# piboy.net
KiCad netlist of a schematic drawn in EAGLE
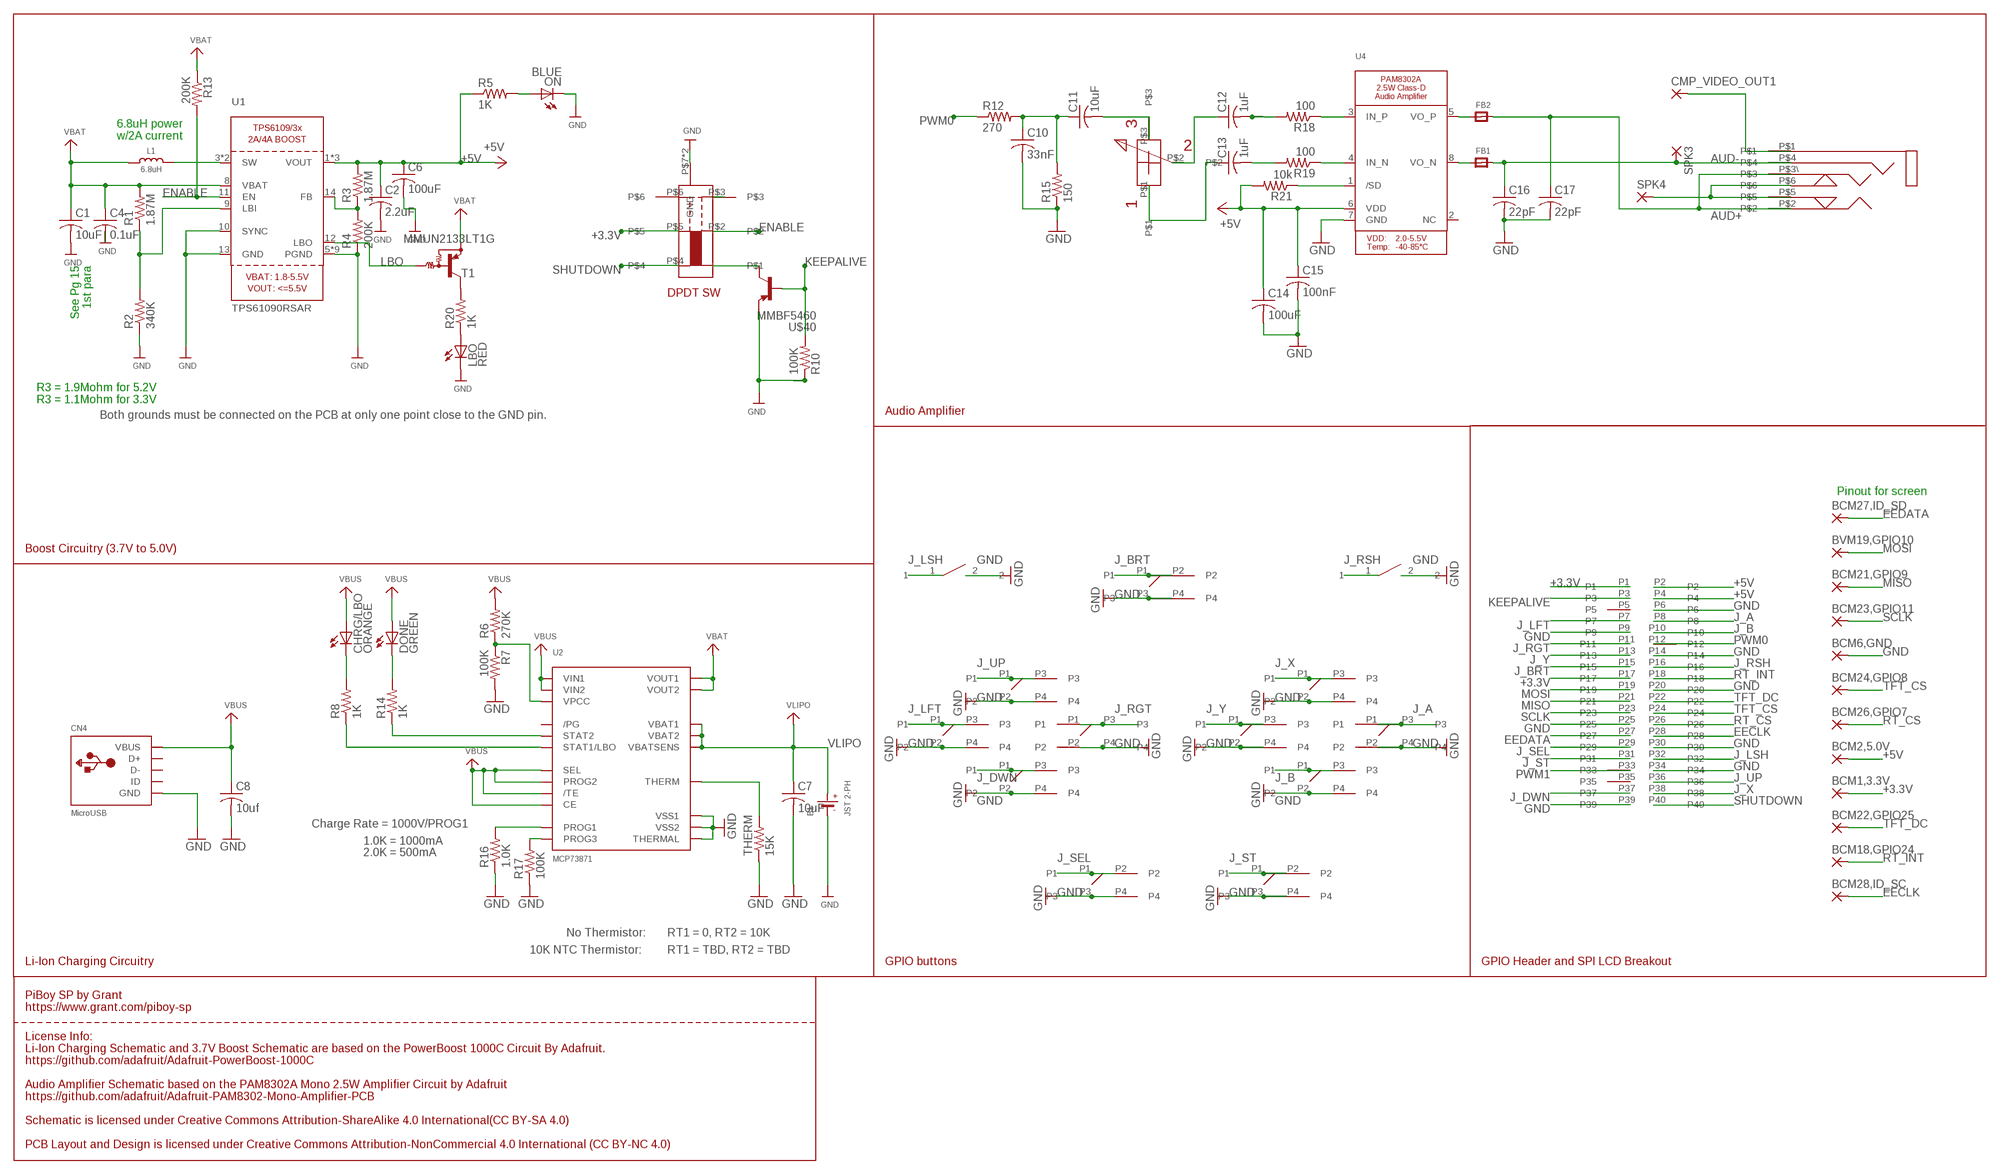
[diagram p0: schematic, sheet 1]

(export (version "E")
  (design (tool "Eeschema 10.0.6"))
  (components
    (comp (ref "B1")
      (value "JST 2-PH")
      (footprint "eagle-import:MICROBUILDER_JSTPH2_NOTHERMALS")
      (libsource (lib "eagle-import") (part "MICROBUILDER_BATTERYPH2_NOTHERMALS"))
    )
    (comp (ref "BCM1,3.3V")
      (value "WIREPAD_1,6/0,9")
      (footprint "eagle-import:WIREPAD_1,6_0,9")
      (libsource (lib "eagle-import") (part "WIREPAD_1,6/0,9"))
    )
    (comp (ref "BCM2,5.0V")
      (value "WIREPAD_1,6/0,9")
      (footprint "eagle-import:WIREPAD_1,6_0,9")
      (libsource (lib "eagle-import") (part "WIREPAD_1,6/0,9"))
    )
    (comp (ref "BCM6,GND")
      (value "WIREPAD_1,6/0,9")
      (footprint "eagle-import:WIREPAD_1,6_0,9")
      (libsource (lib "eagle-import") (part "WIREPAD_1,6/0,9"))
    )
    (comp (ref "BCM18,GPIO24")
      (value "WIREPAD_1,6/0,9")
      (footprint "eagle-import:WIREPAD_1,6_0,9")
      (libsource (lib "eagle-import") (part "WIREPAD_1,6/0,9"))
    )
    (comp (ref "BCM21,GPIO9")
      (value "WIREPAD_1,6/0,9")
      (footprint "eagle-import:WIREPAD_1,6_0,9")
      (libsource (lib "eagle-import") (part "WIREPAD_1,6/0,9"))
    )
    (comp (ref "BCM22,GPIO25")
      (value "WIREPAD_1,6/0,9")
      (footprint "eagle-import:WIREPAD_1,6_0,9")
      (libsource (lib "eagle-import") (part "WIREPAD_1,6/0,9"))
    )
    (comp (ref "BCM23,GPIO11")
      (value "WIREPAD_1,6/0,9")
      (footprint "eagle-import:WIREPAD_1,6_0,9")
      (libsource (lib "eagle-import") (part "WIREPAD_1,6/0,9"))
    )
    (comp (ref "BCM24,GPIO8")
      (value "WIREPAD_1,6/0,9")
      (footprint "eagle-import:WIREPAD_1,6_0,9")
      (libsource (lib "eagle-import") (part "WIREPAD_1,6/0,9"))
    )
    (comp (ref "BCM26,GPIO7")
      (value "WIREPAD_1,6/0,9")
      (footprint "eagle-import:WIREPAD_1,6_0,9")
      (libsource (lib "eagle-import") (part "WIREPAD_1,6/0,9"))
    )
    (comp (ref "BCM27,ID_SD")
      (value "WIREPAD_1,6/0,9")
      (footprint "eagle-import:WIREPAD_1,6_0,9")
      (libsource (lib "eagle-import") (part "WIREPAD_1,6/0,9"))
    )
    (comp (ref "BCM28,ID_SC")
      (value "WIREPAD_1,6/0,9")
      (footprint "eagle-import:WIREPAD_1,6_0,9")
      (libsource (lib "eagle-import") (part "WIREPAD_1,6/0,9"))
    )
    (comp (ref "BVM19,GPIO10")
      (value "WIREPAD_1,6/0,9")
      (footprint "eagle-import:WIREPAD_1,6_0,9")
      (libsource (lib "eagle-import") (part "WIREPAD_1,6/0,9"))
    )
    (comp (ref "C1")
      (value "10uF")
      (footprint "eagle-import:C1210")
      (libsource (lib "eagle-import") (part "resistor_348_C-USC1210"))
    )
    (comp (ref "C2")
      (value "2.2uF")
      (footprint "eagle-import:C0805")
      (libsource (lib "eagle-import") (part "C-USC0805"))
    )
    (comp (ref "C4")
      (value "0.1uF")
      (footprint "eagle-import:C0805")
      (libsource (lib "eagle-import") (part "C-USC0805"))
    )
    (comp (ref "C6")
      (value "100uF")
      (footprint "eagle-import:C1210")
      (libsource (lib "eagle-import") (part "resistor_348_C-USC1210"))
    )
    (comp (ref "C7")
      (value "10uF")
      (footprint "eagle-import:C1210")
      (libsource (lib "eagle-import") (part "resistor_348_C-USC1210"))
    )
    (comp (ref "C8")
      (value "10uf")
      (footprint "eagle-import:C0805")
      (libsource (lib "eagle-import") (part "C-USC0805"))
    )
    (comp (ref "C10")
      (value "33nF")
      (footprint "eagle-import:C0805")
      (libsource (lib "eagle-import") (part "resistor_348_C-USC0805"))
    )
    (comp (ref "C11")
      (value "10uF")
      (footprint "eagle-import:C1210")
      (libsource (lib "eagle-import") (part "resistor_348_C-USC1210"))
    )
    (comp (ref "C12")
      (value "1uF")
      (footprint "eagle-import:C0805")
      (libsource (lib "eagle-import") (part "resistor_348_C-USC0805"))
    )
    (comp (ref "C13")
      (value "1uF")
      (footprint "eagle-import:C0805")
      (libsource (lib "eagle-import") (part "resistor_348_C-USC0805"))
    )
    (comp (ref "C14")
      (value "100uF")
      (footprint "eagle-import:C1210")
      (libsource (lib "eagle-import") (part "resistor_348_C-USC1210"))
    )
    (comp (ref "C15")
      (value "100nF")
      (footprint "eagle-import:C0805")
      (libsource (lib "eagle-import") (part "resistor_348_C-USC0805"))
    )
    (comp (ref "C16")
      (value "22pF")
      (footprint "eagle-import:C0805")
      (libsource (lib "eagle-import") (part "resistor_348_C-USC0805"))
    )
    (comp (ref "C17")
      (value "22pF")
      (footprint "eagle-import:C0805")
      (libsource (lib "eagle-import") (part "resistor_348_C-USC0805"))
    )
    (comp (ref "CHRG/LBO")
      (value "ORANGE")
      (footprint "eagle-import:ADAFRUIT_CHIPLED_0603")
      (libsource (lib "eagle-import") (part "ADAFRUIT_LEDCHIPLED_0603"))
    )
    (comp (ref "CMP_VIDEO_OUT1")
      (value "WIREPAD_1,6/0,9")
      (footprint "eagle-import:WIREPAD_1,6_0,9")
      (libsource (lib "eagle-import") (part "WIREPAD_1,6/0,9"))
    )
    (comp (ref "CN4")
      (value "MicroUSB")
      (footprint "eagle-import:4UCONN_20329")
      (libsource (lib "eagle-import") (part "USBMICRO_20329"))
    )
    (comp (ref "DONE")
      (value "GREEN")
      (footprint "eagle-import:ADAFRUIT_CHIPLED_0603")
      (libsource (lib "eagle-import") (part "ADAFRUIT_LEDCHIPLED_0603"))
    )
    (comp (ref "FB1")
      (value "FERRITE0805")
      (footprint "eagle-import:0805")
      (libsource (lib "eagle-import") (part "FERRITE0805"))
    )
    (comp (ref "FB2")
      (value "FERRITE0805")
      (footprint "eagle-import:0805")
      (libsource (lib "eagle-import") (part "FERRITE0805"))
    )
    (comp (ref "L1")
      (value "6.8uH")
      (footprint "eagle-import:INDUCTOR_5X5MM_TDK_VLC5045")
      (libsource (lib "eagle-import") (part "INDUCTORTDK_VLC5045"))
    )
    (comp (ref "LBO")
      (value "RED")
      (footprint "eagle-import:ADAFRUIT_CHIPLED_0603")
      (libsource (lib "eagle-import") (part "ADAFRUIT_LEDCHIPLED_0603"))
    )
    (comp (ref "ON")
      (value "BLUE")
      (footprint "eagle-import:ADAFRUIT_CHIPLED_0603")
      (libsource (lib "eagle-import") (part "ADAFRUIT_LEDCHIPLED_0603"))
    )
    (comp (ref "R1")
      (value "1.87M")
      (footprint "eagle-import:R0805")
      (libsource (lib "eagle-import") (part "R-US_R0805"))
    )
    (comp (ref "R2")
      (value "340K")
      (footprint "eagle-import:R0805")
      (libsource (lib "eagle-import") (part "R-US_R0805"))
    )
    (comp (ref "R3")
      (value "1.87M")
      (footprint "eagle-import:R0805")
      (libsource (lib "eagle-import") (part "R-US_R0805"))
    )
    (comp (ref "R4")
      (value "200K")
      (footprint "eagle-import:R0805")
      (libsource (lib "eagle-import") (part "R-US_R0805"))
    )
    (comp (ref "R5")
      (value "1K")
      (footprint "eagle-import:R0805")
      (libsource (lib "eagle-import") (part "R-US_R0805"))
    )
    (comp (ref "R6")
      (value "270K")
      (footprint "eagle-import:R0805")
      (libsource (lib "eagle-import") (part "R-US_R0805"))
    )
    (comp (ref "R7")
      (value "100K")
      (footprint "eagle-import:R0805")
      (libsource (lib "eagle-import") (part "R-US_R0805"))
    )
    (comp (ref "R8")
      (value "1K")
      (footprint "eagle-import:R0805")
      (libsource (lib "eagle-import") (part "R-US_R0805"))
    )
    (comp (ref "R10")
      (value "100K")
      (footprint "eagle-import:R0805")
      (libsource (lib "eagle-import") (part "R-US_R0805"))
    )
    (comp (ref "R12")
      (value "270")
      (footprint "eagle-import:R0805")
      (libsource (lib "eagle-import") (part "resistor_348_R-US_R0805"))
    )
    (comp (ref "R13")
      (value "200K")
      (footprint "eagle-import:R0805")
      (libsource (lib "eagle-import") (part "R-US_R0805"))
    )
    (comp (ref "R14")
      (value "1K")
      (footprint "eagle-import:R0805")
      (libsource (lib "eagle-import") (part "R-US_R0805"))
    )
    (comp (ref "R15")
      (value "150")
      (footprint "eagle-import:R0805")
      (libsource (lib "eagle-import") (part "resistor_348_R-US_R0805"))
    )
    (comp (ref "R16")
      (value "1.0K")
      (footprint "eagle-import:R0805")
      (libsource (lib "eagle-import") (part "R-US_R0805"))
    )
    (comp (ref "R17")
      (value "100K")
      (footprint "eagle-import:R0805")
      (libsource (lib "eagle-import") (part "R-US_R0805"))
    )
    (comp (ref "R18")
      (value "100")
      (footprint "eagle-import:R0805")
      (libsource (lib "eagle-import") (part "resistor_348_R-US_R0805"))
    )
    (comp (ref "R19")
      (value "100")
      (footprint "eagle-import:R0805")
      (libsource (lib "eagle-import") (part "resistor_348_R-US_R0805"))
    )
    (comp (ref "R20")
      (value "1K")
      (footprint "eagle-import:R0805")
      (libsource (lib "eagle-import") (part "R-US_R0805"))
    )
    (comp (ref "R21")
      (value "10k")
      (footprint "eagle-import:R0805")
      (libsource (lib "eagle-import") (part "resistor_348_R-US_R0805"))
    )
    (comp (ref "SPK3")
      (value "WIREPAD_1,6/0,9")
      (footprint "eagle-import:WIREPAD_1,6_0,9")
      (libsource (lib "eagle-import") (part "WIREPAD_1,6/0,9"))
    )
    (comp (ref "SPK4")
      (value "WIREPAD_1,6/0,9")
      (footprint "eagle-import:WIREPAD_1,6_0,9")
      (libsource (lib "eagle-import") (part "WIREPAD_1,6/0,9"))
    )
    (comp (ref "T1")
      (value "MMUN2133LT1G")
      (footprint "eagle-import:TRANSISTOR_SC59-BEC")
      (libsource (lib "eagle-import") (part "TRANSISTOR_-PNP_DRIVER-SC59-BECMUN2113T1"))
    )
    (comp (ref "THERM")
      (value "15K")
      (footprint "eagle-import:R0805")
      (libsource (lib "eagle-import") (part "R-US_R0805"))
    )
    (comp (ref "U$9")
      (value "961240-6300-AR-PR")
      (footprint "eagle-import:961240-6300-AR-PR")
      (libsource (lib "eagle-import") (part "961240-6300-AR-PR"))
    )
    (comp (ref "U$10")
      (value "PIBOY_SKRRAAE010")
      (footprint "eagle-import:PIBOY_SKRRAAE010")
      (libsource (lib "eagle-import") (part "PIBOY_SKRRAAE010"))
    )
    (comp (ref "U$11")
      (value "PIBOY_SKRRAAE010")
      (footprint "eagle-import:PIBOY_SKRRAAE010")
      (libsource (lib "eagle-import") (part "PIBOY_SKRRAAE010"))
    )
    (comp (ref "U$12")
      (value "PIBOY_SKRRAAE010")
      (footprint "eagle-import:PIBOY_SKRRAAE010")
      (libsource (lib "eagle-import") (part "PIBOY_SKRRAAE010"))
    )
    (comp (ref "U$13")
      (value "PIBOY_SKRRAAE010")
      (footprint "eagle-import:PIBOY_SKRRAAE010")
      (libsource (lib "eagle-import") (part "PIBOY_SKRRAAE010"))
    )
    (comp (ref "U$15")
      (value "PIBOY_SKRRAAE010")
      (footprint "eagle-import:PIBOY_SKRRAAE010")
      (libsource (lib "eagle-import") (part "PIBOY_SKRRAAE010"))
    )
    (comp (ref "U$16")
      (value "PIBOY_SKRRAAE010")
      (footprint "eagle-import:PIBOY_SKRRAAE010")
      (libsource (lib "eagle-import") (part "PIBOY_SKRRAAE010"))
    )
    (comp (ref "U$17")
      (value "PIBOY_SKRRAAE010")
      (footprint "eagle-import:PIBOY_SKRRAAE010")
      (libsource (lib "eagle-import") (part "PIBOY_SKRRAAE010"))
    )
    (comp (ref "U$18")
      (value "PIBOY_SKRRAAE010")
      (footprint "eagle-import:PIBOY_SKRRAAE010")
      (libsource (lib "eagle-import") (part "PIBOY_SKRRAAE010"))
    )
    (comp (ref "U$21")
      (value "PIBOY_TL3315NF100Q")
      (footprint "eagle-import:PIBOY_TL3315NF100Q")
      (libsource (lib "eagle-import") (part "PIBOY_TL3315NF100Q"))
    )
    (comp (ref "U$22")
      (value "PIBOY_TL3315NF100Q")
      (footprint "eagle-import:PIBOY_TL3315NF100Q")
      (libsource (lib "eagle-import") (part "PIBOY_TL3315NF100Q"))
    )
    (comp (ref "U$25")
      (value "PIBOY_TL3315NF100Q")
      (footprint "eagle-import:PIBOY_TL3315NF100Q")
      (libsource (lib "eagle-import") (part "PIBOY_TL3315NF100Q"))
    )
    (comp (ref "U$26")
      (value "SWITCH_TL1105L-4,3")
      (footprint "eagle-import:SWITCH_TL1105L-4,3")
      (libsource (lib "eagle-import") (part "SWITCH_TL1105L-4,3"))
    )
    (comp (ref "U$28")
      (value "SWITCH_TL1105L-4,3")
      (footprint "eagle-import:SWITCH_TL1105L-4,3")
      (libsource (lib "eagle-import") (part "SWITCH_TL1105L-4,3"))
    )
    (comp (ref "U$29")
      (value "RK10J12R0A0B")
      (footprint "eagle-import:RK10J12R0A0B")
      (libsource (lib "eagle-import") (part "RK10J12R0A0B"))
    )
    (comp (ref "U$30")
      (value "SJ-43504-SMT-TR")
      (footprint "eagle-import:SJ-43504-SMT-TR")
      (libsource (lib "eagle-import") (part "SJ-43504-SMT-TR"))
    )
    (comp (ref "U$31")
      (value "EG2210-SW")
      (footprint "eagle-import:EG2210-SW")
      (libsource (lib "eagle-import") (part "EG2210-SW"))
    )
    (comp (ref "U$40")
      (value "MMBF5460")
      (footprint "eagle-import:SOT23")
      (libsource (lib "eagle-import") (part "MMBF5460"))
    )
    (comp (ref "U1")
      (value "TPS61090RSAR")
      (footprint "eagle-import:PVQFN-16")
      (libsource (lib "eagle-import") (part "VREG_TPS6103X"))
    )
    (comp (ref "U2")
      (value "MCP73871")
      (footprint "eagle-import:QFN20_4MM")
      (libsource (lib "eagle-import") (part "MCP73871"))
    )
    (comp (ref "U4")
      (value "AUDIOAMP_PAM8302A")
      (footprint "eagle-import:MSOP8_0.65MM")
      (libsource (lib "eagle-import") (part "AUDIOAMP_PAM8302A"))
    )
  )
  (nets
    (net (code "1") (name "+5V") (class "Default")
      (node (ref "BCM2,5.0V") (pin "1") (pinfunction "P_1") (pintype "passive"))
      (node (ref "C14") (pin "1") (pinfunction "1_1") (pintype "passive"))
      (node (ref "C15") (pin "1") (pinfunction "1_1") (pintype "passive"))
      (node (ref "C2") (pin "1") (pinfunction "1_1") (pintype "passive"))
      (node (ref "C6") (pin "1") (pinfunction "1_1") (pintype "passive"))
      (node (ref "R21") (pin "2") (pinfunction "2_2") (pintype "passive"))
      (node (ref "R3") (pin "2") (pinfunction "2_2") (pintype "passive"))
      (node (ref "R5") (pin "1") (pinfunction "1_1") (pintype "passive"))
      (node (ref "U$9") (pin "P2") (pinfunction "P2_P2") (pintype "bidirectional"))
      (node (ref "U$9") (pin "P4") (pinfunction "P4_P4") (pintype "bidirectional"))
      (node (ref "U1") (pin "1") (pinfunction "VOUT_1") (pintype "power_in"))
      (node (ref "U1") (pin "15") (pinfunction "VOUT_15") (pintype "power_in"))
      (node (ref "U1") (pin "16") (pinfunction "VOUT_16") (pintype "power_in"))
      (node (ref "U4") (pin "6") (pinfunction "VDD_6") (pintype "power_in"))
    )
    (net (code "2") (name "/+3.3V") (class "Default")
      (node (ref "BCM1,3.3V") (pin "1") (pinfunction "P_1") (pintype "passive"))
      (node (ref "U$31") (pin "P$5") (pinfunction "P$5_P$5") (pintype "bidirectional"))
      (node (ref "U$9") (pin "P1") (pinfunction "P1_P1") (pintype "bidirectional"))
      (node (ref "U$9") (pin "P17") (pinfunction "P17_P17") (pintype "bidirectional"))
    )
    (net (code "3") (name "/AUD+") (class "Default")
      (node (ref "C17") (pin "1") (pinfunction "1_1") (pintype "passive"))
      (node (ref "FB2") (pin "2") (pinfunction "P$2_2") (pintype "passive"))
      (node (ref "U$30") (pin "P$2") (pinfunction "P$2_P$2") (pintype "bidirectional"))
      (node (ref "U$30") (pin "P$3\\") (pinfunction "P$3_P$3\\") (pintype "bidirectional"))
    )
    (net (code "4") (name "/AUD-") (class "Default")
      (node (ref "C16") (pin "1") (pinfunction "1_1") (pintype "passive"))
      (node (ref "FB1") (pin "2") (pinfunction "P$2_2") (pintype "passive"))
      (node (ref "SPK3") (pin "1") (pinfunction "P_1") (pintype "passive"))
      (node (ref "U$30") (pin "P$4") (pinfunction "P$4_P$4") (pintype "bidirectional"))
    )
    (net (code "5") (name "/EECLK") (class "Default")
      (node (ref "BCM28,ID_SC") (pin "1") (pinfunction "P_1") (pintype "passive"))
      (node (ref "U$9") (pin "P28") (pinfunction "P28_P28") (pintype "bidirectional"))
    )
    (net (code "6") (name "/EEDATA") (class "Default")
      (node (ref "BCM27,ID_SD") (pin "1") (pinfunction "P_1") (pintype "passive"))
      (node (ref "U$9") (pin "P27") (pinfunction "P27_P27") (pintype "bidirectional"))
    )
    (net (code "7") (name "/ENABLE") (class "Default")
      (node (ref "R13") (pin "2") (pinfunction "2_2") (pintype "passive"))
      (node (ref "U$31") (pin "P$2") (pinfunction "P$2_P$2") (pintype "bidirectional"))
      (node (ref "U1") (pin "11") (pinfunction "EN_11") (pintype "input"))
    )
    (net (code "8") (name "/J_A") (class "Default")
      (node (ref "U$17") (pin "P1") (pinfunction "P1_P1") (pintype "bidirectional"))
      (node (ref "U$17") (pin "P3") (pinfunction "P3_P3") (pintype "bidirectional"))
      (node (ref "U$9") (pin "P8") (pinfunction "P8_P8") (pintype "bidirectional"))
    )
    (net (code "9") (name "/J_B") (class "Default")
      (node (ref "U$18") (pin "P1") (pinfunction "P1_P1") (pintype "bidirectional"))
      (node (ref "U$18") (pin "P3") (pinfunction "P3_P3") (pintype "bidirectional"))
      (node (ref "U$9") (pin "P10") (pinfunction "P10_P10") (pintype "bidirectional"))
    )
    (net (code "10") (name "/J_BRT") (class "Default")
      (node (ref "U$25") (pin "P1") (pinfunction "P1_P1") (pintype "bidirectional"))
      (node (ref "U$25") (pin "P2") (pinfunction "P2_P2") (pintype "bidirectional"))
      (node (ref "U$9") (pin "P15") (pinfunction "P15_P15") (pintype "bidirectional"))
    )
    (net (code "11") (name "/J_DWN") (class "Default")
      (node (ref "U$13") (pin "P1") (pinfunction "P1_P1") (pintype "bidirectional"))
      (node (ref "U$13") (pin "P3") (pinfunction "P3_P3") (pintype "bidirectional"))
      (node (ref "U$9") (pin "P37") (pinfunction "P37_P37") (pintype "bidirectional"))
    )
    (net (code "12") (name "/J_LFT") (class "Default")
      (node (ref "U$11") (pin "P1") (pinfunction "P1_P1") (pintype "bidirectional"))
      (node (ref "U$11") (pin "P3") (pinfunction "P3_P3") (pintype "bidirectional"))
      (node (ref "U$9") (pin "P7") (pinfunction "P7_P7") (pintype "bidirectional"))
    )
    (net (code "13") (name "/J_LSH") (class "Default")
      (node (ref "U$26") (pin "1") (pinfunction "1_1") (pintype "bidirectional"))
      (node (ref "U$9") (pin "P32") (pinfunction "P32_P32") (pintype "bidirectional"))
    )
    (net (code "14") (name "/J_RGT") (class "Default")
      (node (ref "U$12") (pin "P1") (pinfunction "P1_P1") (pintype "bidirectional"))
      (node (ref "U$12") (pin "P3") (pinfunction "P3_P3") (pintype "bidirectional"))
      (node (ref "U$9") (pin "P11") (pinfunction "P11_P11") (pintype "bidirectional"))
    )
    (net (code "15") (name "/J_RSH") (class "Default")
      (node (ref "U$28") (pin "1") (pinfunction "1_1") (pintype "bidirectional"))
      (node (ref "U$9") (pin "P16") (pinfunction "P16_P16") (pintype "bidirectional"))
    )
    (net (code "16") (name "/J_SEL") (class "Default")
      (node (ref "U$21") (pin "P1") (pinfunction "P1_P1") (pintype "bidirectional"))
      (node (ref "U$21") (pin "P2") (pinfunction "P2_P2") (pintype "bidirectional"))
      (node (ref "U$9") (pin "P29") (pinfunction "P29_P29") (pintype "bidirectional"))
    )
    (net (code "17") (name "/J_ST") (class "Default")
      (node (ref "U$22") (pin "P1") (pinfunction "P1_P1") (pintype "bidirectional"))
      (node (ref "U$22") (pin "P2") (pinfunction "P2_P2") (pintype "bidirectional"))
      (node (ref "U$9") (pin "P31") (pinfunction "P31_P31") (pintype "bidirectional"))
    )
    (net (code "18") (name "/J_UP") (class "Default")
      (node (ref "U$10") (pin "P1") (pinfunction "P1_P1") (pintype "bidirectional"))
      (node (ref "U$10") (pin "P3") (pinfunction "P3_P3") (pintype "bidirectional"))
      (node (ref "U$9") (pin "P36") (pinfunction "P36_P36") (pintype "bidirectional"))
    )
    (net (code "19") (name "/J_X") (class "Default")
      (node (ref "U$15") (pin "P1") (pinfunction "P1_P1") (pintype "bidirectional"))
      (node (ref "U$15") (pin "P3") (pinfunction "P3_P3") (pintype "bidirectional"))
      (node (ref "U$9") (pin "P38") (pinfunction "P38_P38") (pintype "bidirectional"))
    )
    (net (code "20") (name "/J_Y") (class "Default")
      (node (ref "U$16") (pin "P1") (pinfunction "P1_P1") (pintype "bidirectional"))
      (node (ref "U$16") (pin "P3") (pinfunction "P3_P3") (pintype "bidirectional"))
      (node (ref "U$9") (pin "P13") (pinfunction "P13_P13") (pintype "bidirectional"))
    )
    (net (code "21") (name "/KEEPALIVE") (class "Default")
      (node (ref "R10") (pin "2") (pinfunction "2_2") (pintype "passive"))
      (node (ref "U$40") (pin "3") (pinfunction "G_3") (pintype "passive"))
      (node (ref "U$9") (pin "P3") (pinfunction "P3_P3") (pintype "bidirectional"))
    )
    (net (code "22") (name "/LBO") (class "Default")
      (node (ref "T1") (pin "B") (pinfunction "B_B") (pintype "passive"))
      (node (ref "U1") (pin "12") (pinfunction "LBO_12") (pintype "output"))
    )
    (net (code "23") (name "/MISO") (class "Default")
      (node (ref "BCM21,GPIO9") (pin "1") (pinfunction "P_1") (pintype "passive"))
      (node (ref "U$9") (pin "P21") (pinfunction "P21_P21") (pintype "bidirectional"))
    )
    (net (code "24") (name "/MOSI") (class "Default")
      (node (ref "BVM19,GPIO10") (pin "1") (pinfunction "P_1") (pintype "passive"))
      (node (ref "U$9") (pin "P19") (pinfunction "P19_P19") (pintype "bidirectional"))
    )
    (net (code "25") (name "/PWM0") (class "Default")
      (node (ref "R12") (pin "1") (pinfunction "1_1") (pintype "passive"))
      (node (ref "U$9") (pin "P12") (pinfunction "P12_P12") (pintype "bidirectional"))
    )
    (net (code "26") (name "/PWM1") (class "Default")
      (node (ref "U$9") (pin "P33") (pinfunction "P33_P33") (pintype "bidirectional"))
    )
    (net (code "27") (name "/RT_CS") (class "Default")
      (node (ref "BCM26,GPIO7") (pin "1") (pinfunction "P_1") (pintype "passive"))
      (node (ref "U$9") (pin "P26") (pinfunction "P26_P26") (pintype "bidirectional"))
    )
    (net (code "28") (name "/RT_INT") (class "Default")
      (node (ref "BCM18,GPIO24") (pin "1") (pinfunction "P_1") (pintype "passive"))
      (node (ref "U$9") (pin "P18") (pinfunction "P18_P18") (pintype "bidirectional"))
    )
    (net (code "29") (name "/SCLK") (class "Default")
      (node (ref "BCM23,GPIO11") (pin "1") (pinfunction "P_1") (pintype "passive"))
      (node (ref "U$9") (pin "P23") (pinfunction "P23_P23") (pintype "bidirectional"))
    )
    (net (code "30") (name "/SHUTDOWN") (class "Default")
      (node (ref "U$31") (pin "P$4") (pinfunction "P$4_P$4") (pintype "bidirectional"))
      (node (ref "U$9") (pin "P40") (pinfunction "P40_P40") (pintype "bidirectional"))
    )
    (net (code "31") (name "/TFT_CS") (class "Default")
      (node (ref "BCM24,GPIO8") (pin "1") (pinfunction "P_1") (pintype "passive"))
      (node (ref "U$9") (pin "P24") (pinfunction "P24_P24") (pintype "bidirectional"))
    )
    (net (code "32") (name "/TFT_DC") (class "Default")
      (node (ref "BCM22,GPIO25") (pin "1") (pinfunction "P_1") (pintype "passive"))
      (node (ref "U$9") (pin "P22") (pinfunction "P22_P22") (pintype "bidirectional"))
    )
    (net (code "33") (name "GND") (class "Default")
      (node (ref "B1") (pin "1") (pinfunction "-_1") (pintype "passive"))
      (node (ref "B1") (pin "NC1") (pinfunction "-_NC1") (pintype "passive"))
      (node (ref "B1") (pin "NC2") (pinfunction "-_NC2") (pintype "passive"))
      (node (ref "BCM6,GND") (pin "1") (pinfunction "P_1") (pintype "passive"))
      (node (ref "C1") (pin "2") (pinfunction "2_2") (pintype "passive"))
      (node (ref "C10") (pin "2") (pinfunction "2_2") (pintype "passive"))
      (node (ref "C14") (pin "2") (pinfunction "2_2") (pintype "passive"))
      (node (ref "C15") (pin "2") (pinfunction "2_2") (pintype "passive"))
      (node (ref "C16") (pin "2") (pinfunction "2_2") (pintype "passive"))
      (node (ref "C17") (pin "2") (pinfunction "2_2") (pintype "passive"))
      (node (ref "C2") (pin "2") (pinfunction "2_2") (pintype "passive"))
      (node (ref "C4") (pin "2") (pinfunction "2_2") (pintype "passive"))
      (node (ref "C6") (pin "2") (pinfunction "2_2") (pintype "passive"))
      (node (ref "C7") (pin "2") (pinfunction "2_2") (pintype "passive"))
      (node (ref "C8") (pin "2") (pinfunction "2_2") (pintype "passive"))
      (node (ref "CN4") (pin "BASE@1") (pinfunction "GND_BASE@1") (pintype "power_in"))
      (node (ref "CN4") (pin "BASE@2") (pinfunction "GND_BASE@2") (pintype "power_in"))
      (node (ref "CN4") (pin "GND") (pinfunction "GND_GND") (pintype "power_in"))
      (node (ref "CN4") (pin "SPRT@1") (pinfunction "GND_SPRT@1") (pintype "power_in"))
      (node (ref "CN4") (pin "SPRT@2") (pinfunction "GND_SPRT@2") (pintype "power_in"))
      (node (ref "CN4") (pin "SPRT@3") (pinfunction "GND_SPRT@3") (pintype "power_in"))
      (node (ref "CN4") (pin "SPRT@4") (pinfunction "GND_SPRT@4") (pintype "power_in"))
      (node (ref "LBO") (pin "C") (pinfunction "C_C") (pintype "passive"))
      (node (ref "ON") (pin "C") (pinfunction "C_C") (pintype "passive"))
      (node (ref "R10") (pin "1") (pinfunction "1_1") (pintype "passive"))
      (node (ref "R15") (pin "1") (pinfunction "1_1") (pintype "passive"))
      (node (ref "R16") (pin "1") (pinfunction "1_1") (pintype "passive"))
      (node (ref "R17") (pin "1") (pinfunction "1_1") (pintype "passive"))
      (node (ref "R2") (pin "1") (pinfunction "1_1") (pintype "passive"))
      (node (ref "R4") (pin "1") (pinfunction "1_1") (pintype "passive"))
      (node (ref "R7") (pin "2") (pinfunction "2_2") (pintype "passive"))
      (node (ref "THERM") (pin "1") (pinfunction "1_1") (pintype "passive"))
      (node (ref "U$10") (pin "P2") (pinfunction "P2_P2") (pintype "bidirectional"))
      (node (ref "U$10") (pin "P4") (pinfunction "P4_P4") (pintype "bidirectional"))
      (node (ref "U$11") (pin "P2") (pinfunction "P2_P2") (pintype "bidirectional"))
      (node (ref "U$11") (pin "P4") (pinfunction "P4_P4") (pintype "bidirectional"))
      (node (ref "U$12") (pin "P2") (pinfunction "P2_P2") (pintype "bidirectional"))
      (node (ref "U$12") (pin "P4") (pinfunction "P4_P4") (pintype "bidirectional"))
      (node (ref "U$13") (pin "P2") (pinfunction "P2_P2") (pintype "bidirectional"))
      (node (ref "U$13") (pin "P4") (pinfunction "P4_P4") (pintype "bidirectional"))
      (node (ref "U$15") (pin "P2") (pinfunction "P2_P2") (pintype "bidirectional"))
      (node (ref "U$15") (pin "P4") (pinfunction "P4_P4") (pintype "bidirectional"))
      (node (ref "U$16") (pin "P2") (pinfunction "P2_P2") (pintype "bidirectional"))
      (node (ref "U$16") (pin "P4") (pinfunction "P4_P4") (pintype "bidirectional"))
      (node (ref "U$17") (pin "P2") (pinfunction "P2_P2") (pintype "bidirectional"))
      (node (ref "U$17") (pin "P4") (pinfunction "P4_P4") (pintype "bidirectional"))
      (node (ref "U$18") (pin "P2") (pinfunction "P2_P2") (pintype "bidirectional"))
      (node (ref "U$18") (pin "P4") (pinfunction "P4_P4") (pintype "bidirectional"))
      (node (ref "U$21") (pin "P3") (pinfunction "P3_P3") (pintype "bidirectional"))
      (node (ref "U$21") (pin "P4") (pinfunction "P4_P4") (pintype "bidirectional"))
      (node (ref "U$22") (pin "P3") (pinfunction "P3_P3") (pintype "bidirectional"))
      (node (ref "U$22") (pin "P4") (pinfunction "P4_P4") (pintype "bidirectional"))
      (node (ref "U$25") (pin "P3") (pinfunction "P3_P3") (pintype "bidirectional"))
      (node (ref "U$25") (pin "P4") (pinfunction "P4_P4") (pintype "bidirectional"))
      (node (ref "U$26") (pin "2") (pinfunction "2_2") (pintype "bidirectional"))
      (node (ref "U$28") (pin "2") (pinfunction "2_2") (pintype "bidirectional"))
      (node (ref "U$31") (pin "P$7") (pinfunction "GND_P$7") (pintype "power_in"))
      (node (ref "U$31") (pin "P$8") (pinfunction "GND_P$8") (pintype "power_in"))
      (node (ref "U$40") (pin "2") (pinfunction "S_2") (pintype "passive"))
      (node (ref "U$9") (pin "P14") (pinfunction "P14_P14") (pintype "bidirectional"))
      (node (ref "U$9") (pin "P20") (pinfunction "P20_P20") (pintype "bidirectional"))
      (node (ref "U$9") (pin "P25") (pinfunction "P25_P25") (pintype "bidirectional"))
      (node (ref "U$9") (pin "P30") (pinfunction "P30_P30") (pintype "bidirectional"))
      (node (ref "U$9") (pin "P34") (pinfunction "P34_P34") (pintype "bidirectional"))
      (node (ref "U$9") (pin "P39") (pinfunction "P39_P39") (pintype "bidirectional"))
      (node (ref "U$9") (pin "P6") (pinfunction "P6_P6") (pintype "bidirectional"))
      (node (ref "U$9") (pin "P9") (pinfunction "P9_P9") (pintype "bidirectional"))
      (node (ref "U1") (pin "10") (pinfunction "SYNC_10") (pintype "input"))
      (node (ref "U1") (pin "13") (pinfunction "GND_13") (pintype "power_in"))
      (node (ref "U1") (pin "5") (pinfunction "PGND_5") (pintype "power_in"))
      (node (ref "U1") (pin "6") (pinfunction "PGND_6") (pintype "power_in"))
      (node (ref "U1") (pin "7") (pinfunction "PGND_7") (pintype "power_in"))
      (node (ref "U1") (pin "P$18") (pinfunction "PGND_P$18") (pintype "power_in"))
      (node (ref "U1") (pin "P$19") (pinfunction "PGND_P$19") (pintype "power_in"))
      (node (ref "U1") (pin "P$20") (pinfunction "PGND_P$20") (pintype "power_in"))
      (node (ref "U1") (pin "P$21") (pinfunction "PGND_P$21") (pintype "power_in"))
      (node (ref "U1") (pin "P$22") (pinfunction "PGND_P$22") (pintype "power_in"))
      (node (ref "U1") (pin "THERMAL") (pinfunction "PGND_THERMAL") (pintype "power_in"))
      (node (ref "U2") (pin "P$10") (pinfunction "VSS1_P$10") (pintype "bidirectional"))
      (node (ref "U2") (pin "P$11") (pinfunction "VSS2_P$11") (pintype "bidirectional"))
      (node (ref "U2") (pin "P$21") (pinfunction "THERMAL_P$21") (pintype "bidirectional"))
      (node (ref "U4") (pin "7") (pinfunction "GND_7") (pintype "power_in"))
    )
    (net (code "34") (name "Net-(C10-Pad1)") (class "Default")
      (node (ref "C10") (pin "1") (pinfunction "1_1") (pintype "passive"))
      (node (ref "C11") (pin "1") (pinfunction "1_1") (pintype "passive"))
      (node (ref "R12") (pin "2") (pinfunction "2_2") (pintype "passive"))
      (node (ref "R15") (pin "2") (pinfunction "2_2") (pintype "passive"))
    )
    (net (code "35") (name "Net-(C11-Pad2)") (class "Default")
      (node (ref "C11") (pin "2") (pinfunction "2_2") (pintype "passive"))
      (node (ref "U$29") (pin "P$3") (pinfunction "P$3_P$3") (pintype "bidirectional"))
    )
    (net (code "36") (name "Net-(C12-Pad1)") (class "Default")
      (node (ref "C12") (pin "1") (pinfunction "1_1") (pintype "passive"))
      (node (ref "U$29") (pin "P$2") (pinfunction "P$2_P$2") (pintype "bidirectional"))
    )
    (net (code "37") (name "Net-(C12-Pad2)") (class "Default")
      (node (ref "C12") (pin "2") (pinfunction "2_2") (pintype "passive"))
      (node (ref "R18") (pin "2") (pinfunction "2_2") (pintype "passive"))
    )
    (net (code "38") (name "Net-(C13-Pad1)") (class "Default")
      (node (ref "C13") (pin "1") (pinfunction "1_1") (pintype "passive"))
      (node (ref "U$29") (pin "P$1") (pinfunction "P$1_P$1") (pintype "bidirectional"))
    )
    (net (code "39") (name "Net-(C13-Pad2)") (class "Default")
      (node (ref "C13") (pin "2") (pinfunction "2_2") (pintype "passive"))
      (node (ref "R19") (pin "2") (pinfunction "2_2") (pintype "passive"))
    )
    (net (code "40") (name "Net-(CHRG/LBO-PadC)") (class "Default")
      (node (ref "CHRG/LBO") (pin "C") (pinfunction "C_C") (pintype "passive"))
      (node (ref "R8") (pin "2") (pinfunction "2_2") (pintype "passive"))
    )
    (net (code "41") (name "Net-(CMP_VIDEO_OUT1-P)") (class "Default")
      (node (ref "CMP_VIDEO_OUT1") (pin "1") (pinfunction "P_1") (pintype "passive"))
      (node (ref "U$30") (pin "P$1") (pinfunction "P$1_P$1") (pintype "bidirectional"))
    )
    (net (code "42") (name "Net-(DONE-PadC)") (class "Default")
      (node (ref "DONE") (pin "C") (pinfunction "C_C") (pintype "passive"))
      (node (ref "R14") (pin "2") (pinfunction "2_2") (pintype "passive"))
    )
    (net (code "43") (name "Net-(FB1-P$1)") (class "Default")
      (node (ref "FB1") (pin "1") (pinfunction "P$1_1") (pintype "passive"))
      (node (ref "U4") (pin "8") (pinfunction "VO_N_8") (pintype "output"))
    )
    (net (code "44") (name "Net-(FB2-P$1)") (class "Default")
      (node (ref "FB2") (pin "1") (pinfunction "P$1_1") (pintype "passive"))
      (node (ref "U4") (pin "5") (pinfunction "VO_P_5") (pintype "output"))
    )
    (net (code "45") (name "Net-(L1-2)") (class "Default")
      (node (ref "L1") (pin "P$2") (pinfunction "2_P$2") (pintype "passive"))
      (node (ref "U1") (pin "3") (pinfunction "SW_3") (pintype "input"))
      (node (ref "U1") (pin "4") (pinfunction "SW_4") (pintype "input"))
    )
    (net (code "46") (name "Net-(LBO-PadA)") (class "Default")
      (node (ref "LBO") (pin "A") (pinfunction "A_A") (pintype "passive"))
      (node (ref "R20") (pin "1") (pinfunction "1_1") (pintype "passive"))
    )
    (net (code "47") (name "Net-(ON-PadA)") (class "Default")
      (node (ref "ON") (pin "A") (pinfunction "A_A") (pintype "passive"))
      (node (ref "R5") (pin "2") (pinfunction "2_2") (pintype "passive"))
    )
    (net (code "48") (name "Net-(R20-Pad2)") (class "Default")
      (node (ref "R20") (pin "2") (pinfunction "2_2") (pintype "passive"))
      (node (ref "T1") (pin "C") (pinfunction "C_C") (pintype "passive"))
    )
    (net (code "49") (name "Net-(SPK4-P)") (class "Default")
      (node (ref "SPK4") (pin "1") (pinfunction "P_1") (pintype "passive"))
      (node (ref "U$30") (pin "P$5") (pinfunction "P$5_P$5") (pintype "bidirectional"))
      (node (ref "U$30") (pin "P$6") (pinfunction "P$6_P$6") (pintype "bidirectional"))
    )
    (net (code "50") (name "Net-(U$40-D)") (class "Default")
      (node (ref "U$31") (pin "P$1") (pinfunction "P$1_P$1") (pintype "bidirectional"))
      (node (ref "U$40") (pin "1") (pinfunction "D_1") (pintype "passive"))
    )
    (net (code "51") (name "Net-(U1-FB)") (class "Default")
      (node (ref "R3") (pin "1") (pinfunction "1_1") (pintype "passive"))
      (node (ref "R4") (pin "2") (pinfunction "2_2") (pintype "passive"))
      (node (ref "U1") (pin "14") (pinfunction "FB_14") (pintype "input"))
    )
    (net (code "52") (name "Net-(U1-LBI)") (class "Default")
      (node (ref "R1") (pin "1") (pinfunction "1_1") (pintype "passive"))
      (node (ref "R2") (pin "2") (pinfunction "2_2") (pintype "passive"))
      (node (ref "U1") (pin "9") (pinfunction "LBI_9") (pintype "input"))
    )
    (net (code "53") (name "Net-(U2-PROG1)") (class "Default")
      (node (ref "R16") (pin "2") (pinfunction "2_2") (pintype "passive"))
      (node (ref "U2") (pin "P$13") (pinfunction "PROG1_P$13") (pintype "bidirectional"))
    )
    (net (code "54") (name "Net-(U2-PROG3)") (class "Default")
      (node (ref "R17") (pin "2") (pinfunction "2_2") (pintype "passive"))
      (node (ref "U2") (pin "P$12") (pinfunction "PROG3_P$12") (pintype "bidirectional"))
    )
    (net (code "55") (name "Net-(U2-STAT1{slash}LBO)") (class "Default")
      (node (ref "R8") (pin "1") (pinfunction "1_1") (pintype "passive"))
      (node (ref "U2") (pin "P$8") (pinfunction "STAT1/LBO_P$8") (pintype "bidirectional"))
    )
    (net (code "56") (name "Net-(U2-STAT2)") (class "Default")
      (node (ref "R14") (pin "1") (pinfunction "1_1") (pintype "passive"))
      (node (ref "U2") (pin "P$7") (pinfunction "STAT2_P$7") (pintype "bidirectional"))
    )
    (net (code "57") (name "Net-(U2-THERM)") (class "Default")
      (node (ref "THERM") (pin "2") (pinfunction "2_2") (pintype "passive"))
      (node (ref "U2") (pin "P$5") (pinfunction "THERM_P$5") (pintype "bidirectional"))
    )
    (net (code "58") (name "Net-(U2-VPCC)") (class "Default")
      (node (ref "R6") (pin "1") (pinfunction "1_1") (pintype "passive"))
      (node (ref "R7") (pin "1") (pinfunction "1_1") (pintype "passive"))
      (node (ref "U2") (pin "P$2") (pinfunction "VPCC_P$2") (pintype "bidirectional"))
    )
    (net (code "59") (name "Net-(U4-IN_N)") (class "Default")
      (node (ref "R19") (pin "1") (pinfunction "1_1") (pintype "passive"))
      (node (ref "U4") (pin "4") (pinfunction "IN_N_4") (pintype "input"))
    )
    (net (code "60") (name "Net-(U4-IN_P)") (class "Default")
      (node (ref "R18") (pin "1") (pinfunction "1_1") (pintype "passive"))
      (node (ref "U4") (pin "3") (pinfunction "IN_P_3") (pintype "input"))
    )
    (net (code "61") (name "Net-(U4-{slash}SD)") (class "Default")
      (node (ref "R21") (pin "1") (pinfunction "1_1") (pintype "passive"))
      (node (ref "U4") (pin "1") (pinfunction "/SD_1") (pintype "input"))
    )
    (net (code "62") (name "VBAT") (class "Default")
      (node (ref "C1") (pin "1") (pinfunction "1_1") (pintype "passive"))
      (node (ref "C4") (pin "1") (pinfunction "1_1") (pintype "passive"))
      (node (ref "L1") (pin "P$1") (pinfunction "1_P$1") (pintype "passive"))
      (node (ref "R1") (pin "2") (pinfunction "2_2") (pintype "passive"))
      (node (ref "R13") (pin "1") (pinfunction "1_1") (pintype "passive"))
      (node (ref "T1") (pin "E") (pinfunction "E_E") (pintype "passive"))
      (node (ref "U1") (pin "8") (pinfunction "VBAT_8") (pintype "input"))
      (node (ref "U2") (pin "P$1") (pinfunction "VOUT1_P$1") (pintype "bidirectional"))
      (node (ref "U2") (pin "P$20") (pinfunction "VOUT2_P$20") (pintype "bidirectional"))
    )
    (net (code "63") (name "VBUS") (class "Default")
      (node (ref "C8") (pin "1") (pinfunction "1_1") (pintype "passive"))
      (node (ref "CHRG/LBO") (pin "A") (pinfunction "A_A") (pintype "passive"))
      (node (ref "CN4") (pin "VBUS") (pinfunction "VBUS_VBUS") (pintype "power_in"))
      (node (ref "DONE") (pin "A") (pinfunction "A_A") (pintype "passive"))
      (node (ref "R6") (pin "2") (pinfunction "2_2") (pintype "passive"))
      (node (ref "U2") (pin "P$17") (pinfunction "CE_P$17") (pintype "bidirectional"))
      (node (ref "U2") (pin "P$18") (pinfunction "VIN1_P$18") (pintype "bidirectional"))
      (node (ref "U2") (pin "P$19") (pinfunction "VIN2_P$19") (pintype "bidirectional"))
      (node (ref "U2") (pin "P$3") (pinfunction "SEL_P$3") (pintype "bidirectional"))
      (node (ref "U2") (pin "P$4") (pinfunction "PROG2_P$4") (pintype "bidirectional"))
      (node (ref "U2") (pin "P$9") (pinfunction "/TE_P$9") (pintype "bidirectional"))
    )
    (net (code "64") (name "VLIPO") (class "Default")
      (node (ref "B1") (pin "2") (pinfunction "+_2") (pintype "passive"))
      (node (ref "C7") (pin "1") (pinfunction "1_1") (pintype "passive"))
      (node (ref "U2") (pin "P$14") (pinfunction "VBAT1_P$14") (pintype "bidirectional"))
      (node (ref "U2") (pin "P$15") (pinfunction "VBAT2_P$15") (pintype "bidirectional"))
      (node (ref "U2") (pin "P$16") (pinfunction "VBATSENS_P$16") (pintype "bidirectional"))
    )
    (net (code "65") (name "unconnected-(CN4-PadD+)") (class "Default")
      (node (ref "CN4") (pin "D+") (pinfunction "D+_D+") (pintype "bidirectional"))
    )
    (net (code "66") (name "unconnected-(CN4-PadD-)") (class "Default")
      (node (ref "CN4") (pin "D-") (pinfunction "D-_D-") (pintype "bidirectional"))
    )
    (net (code "67") (name "unconnected-(CN4-PadID)") (class "Default")
      (node (ref "CN4") (pin "ID") (pinfunction "ID_ID") (pintype "bidirectional"))
    )
    (net (code "68") (name "unconnected-(U$9-PadP5)") (class "Default")
      (node (ref "U$9") (pin "P5") (pinfunction "P5_P5") (pintype "bidirectional"))
    )
    (net (code "69") (name "unconnected-(U$9-PadP35)") (class "Default")
      (node (ref "U$9") (pin "P35") (pinfunction "P35_P35") (pintype "bidirectional"))
    )
    (net (code "70") (name "unconnected-(U$31-PadP$3)") (class "Default")
      (node (ref "U$31") (pin "P$3") (pinfunction "P$3_P$3") (pintype "bidirectional"))
    )
    (net (code "71") (name "unconnected-(U$31-PadP$6)") (class "Default")
      (node (ref "U$31") (pin "P$6") (pinfunction "P$6_P$6") (pintype "bidirectional"))
    )
    (net (code "72") (name "unconnected-(U2-{slash}PG-PadP$6)") (class "Default")
      (node (ref "U2") (pin "P$6") (pinfunction "/PG_P$6") (pintype "bidirectional"))
    )
    (net (code "73") (name "unconnected-(U4-NC-Pad2)") (class "Default")
      (node (ref "U4") (pin "2") (pinfunction "NC_2") (pintype "no_connect"))
    )
  )
)
